# Hydra_OSP.net
KiCad netlist of a schematic drawn in EAGLE
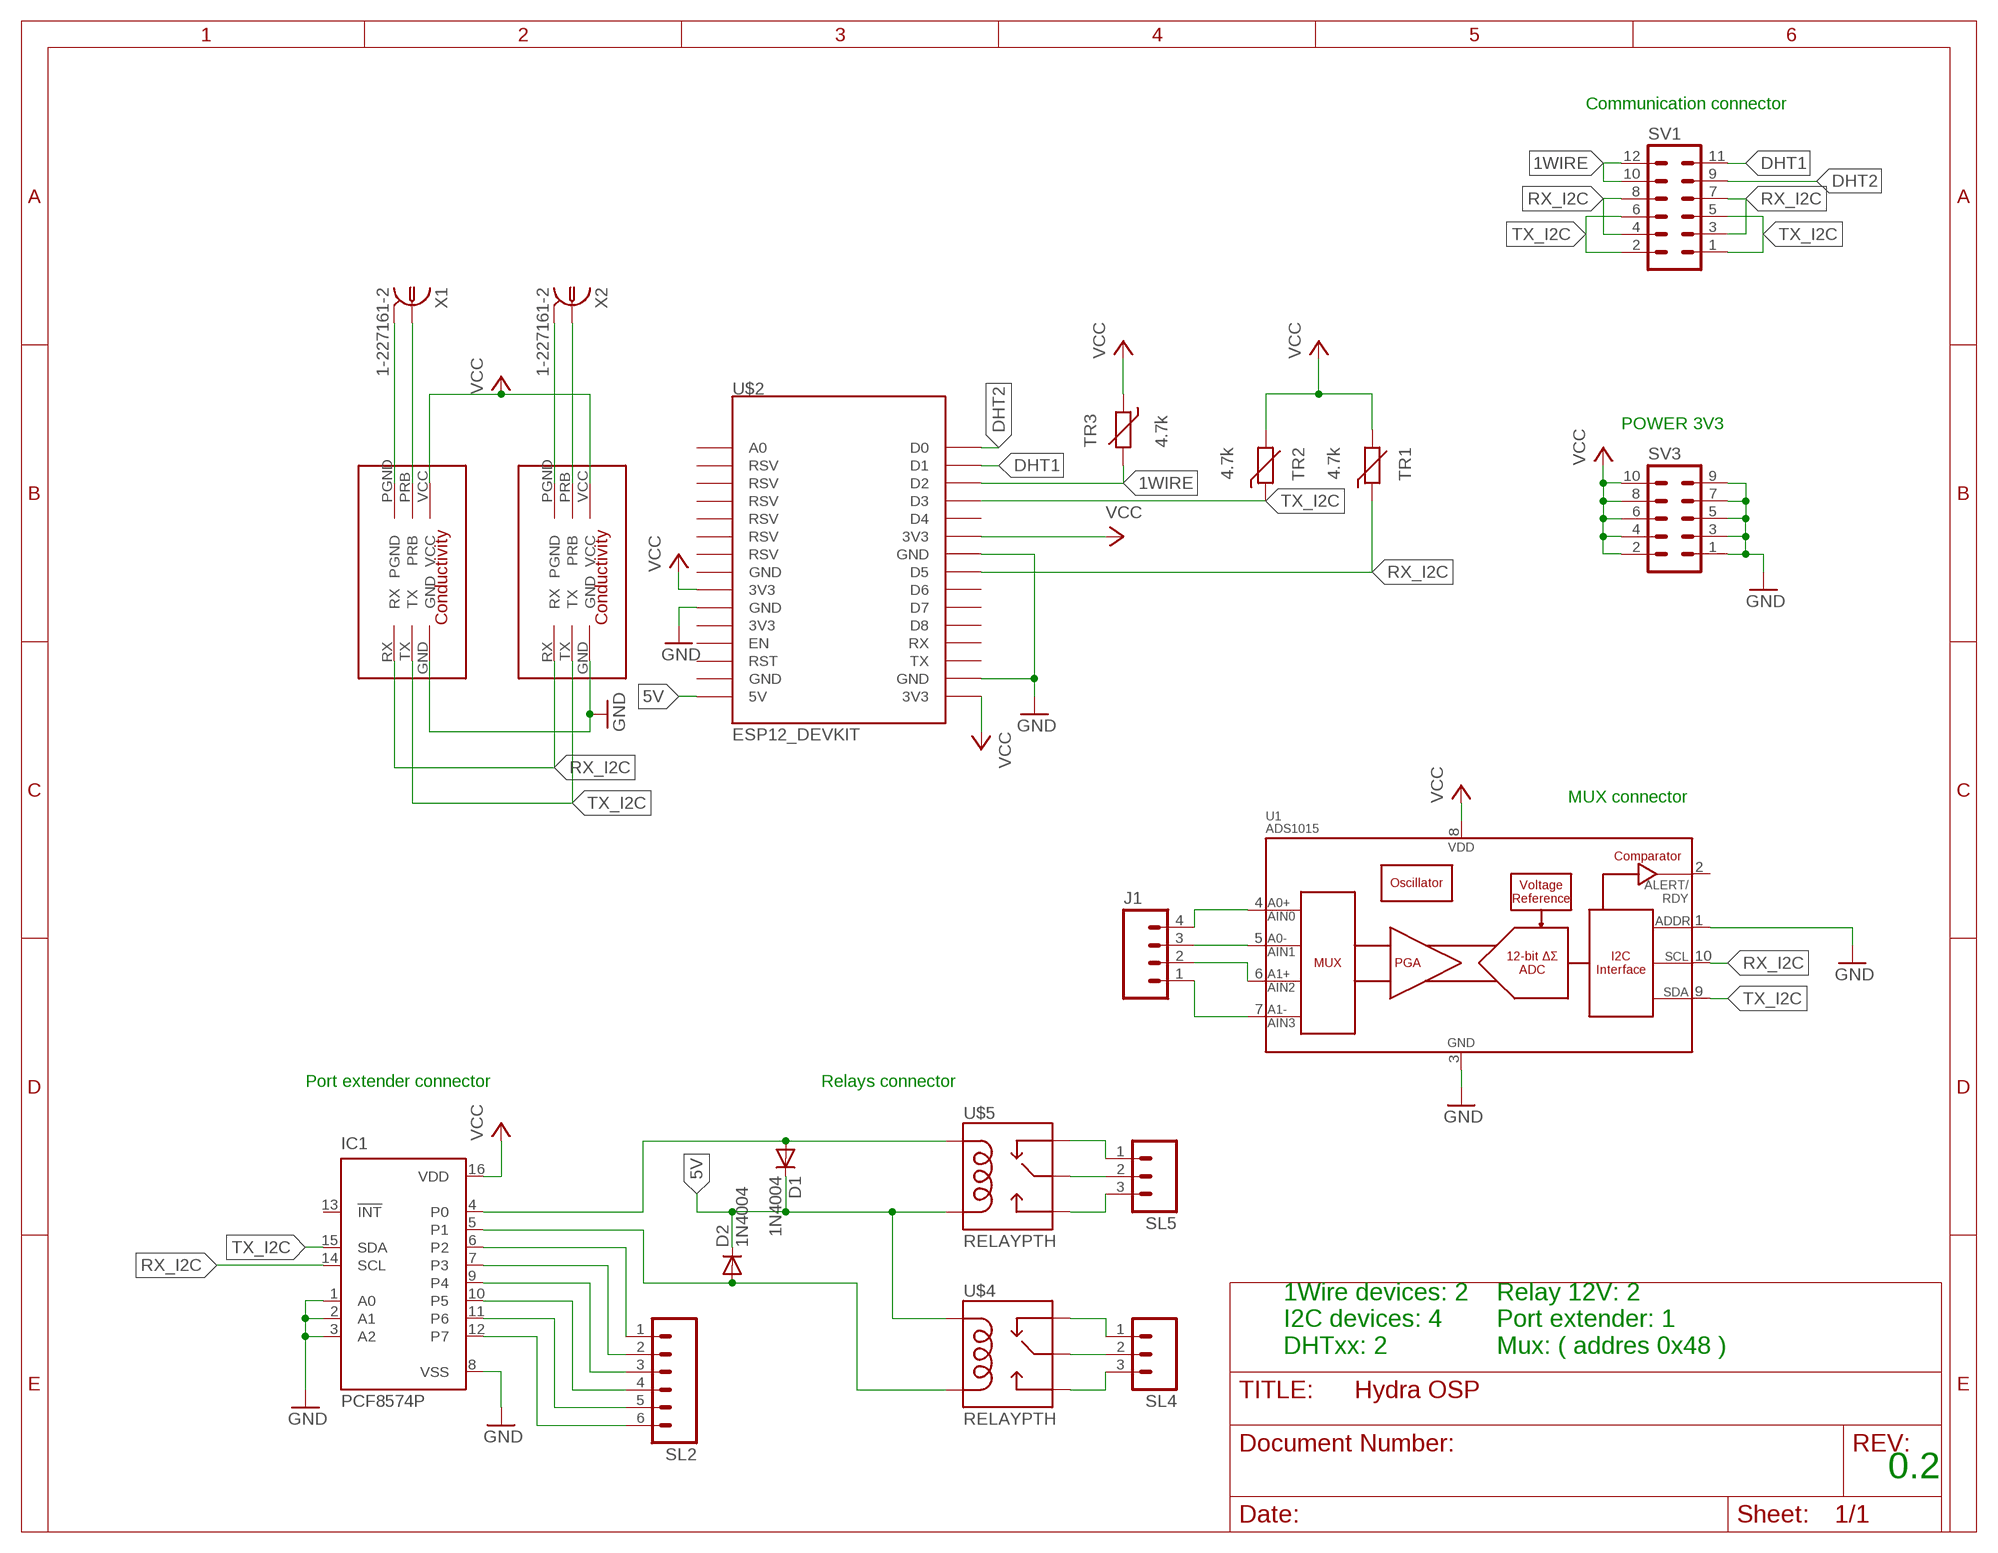
[diagram p0: schematic, sheet 1]

(export (version "E")
  (design (tool "Eeschema 10.0.6"))
  (components
    (comp (ref "D1")
      (value "1N4004")
      (footprint "eagle-import:DO41-10")
      (libsource (lib "eagle-import") (part "1N4004"))
    )
    (comp (ref "D2")
      (value "1N4004")
      (footprint "eagle-import:DO41-10")
      (libsource (lib "eagle-import") (part "1N4004"))
    )
    (comp (ref "IC1")
      (value "PCF8574P")
      (footprint "eagle-import:DIL16")
      (fields (field (name "MPN") "PCF8574PN"))
      (libsource (lib "eagle-import") (part "PCF8574P"))
    )
    (comp (ref "J1")
      (value "M04LOCK")
      (footprint "eagle-import:1X04_LOCK")
      (libsource (lib "eagle-import") (part "M04LOCK"))
    )
    (comp (ref "SL2")
      (value "M06")
      (footprint "eagle-import:06P")
      (libsource (lib "eagle-import") (part "M06"))
    )
    (comp (ref "SL4")
      (value "M03")
      (footprint "eagle-import:03P")
      (libsource (lib "eagle-import") (part "M03"))
    )
    (comp (ref "SL5")
      (value "M03")
      (footprint "eagle-import:03P")
      (libsource (lib "eagle-import") (part "M03"))
    )
    (comp (ref "SV1")
      (value "MA06-2")
      (footprint "eagle-import:MA06-2")
      (libsource (lib "eagle-import") (part "MA06-2"))
    )
    (comp (ref "SV3")
      (value "MA05-2")
      (footprint "eagle-import:MA05-2")
      (libsource (lib "eagle-import") (part "MA05-2"))
    )
    (comp (ref "TR1")
      (value "4.7k")
      (footprint "eagle-import:R-5")
      (libsource (lib "eagle-import") (part "THERMISTOR_R-5"))
    )
    (comp (ref "TR2")
      (value "4.7k")
      (footprint "eagle-import:R-5")
      (libsource (lib "eagle-import") (part "THERMISTOR_R-5"))
    )
    (comp (ref "TR3")
      (value "4.7k")
      (footprint "eagle-import:R-5")
      (libsource (lib "eagle-import") (part "THERMISTOR_R-5"))
    )
    (comp (ref "U$1")
      (value "ATLSCI_COND")
      (footprint "eagle-import:ATLAS_SCI_COND")
      (libsource (lib "eagle-import") (part "ATLSCI_COND"))
    )
    (comp (ref "U$2")
      (value "ESP12_DEVKIT")
      (footprint "eagle-import:ESP12_DEVKIT")
      (libsource (lib "eagle-import") (part "ESP12_DEVKIT"))
    )
    (comp (ref "U$3")
      (value "ATLSCI_COND")
      (footprint "eagle-import:ATLAS_SCI_COND")
      (libsource (lib "eagle-import") (part "ATLSCI_COND"))
    )
    (comp (ref "U$4")
      (value "RELAYPTH")
      (footprint "eagle-import:SRD-05VDC-SL-C")
      (libsource (lib "eagle-import") (part "RELAYPTH"))
    )
    (comp (ref "U$5")
      (value "RELAYPTH")
      (footprint "eagle-import:SRD-05VDC-SL-C")
      (libsource (lib "eagle-import") (part "RELAYPTH"))
    )
    (comp (ref "U1")
      (value "ADS1015")
      (footprint "eagle-import:MSOP10")
      (libsource (lib "eagle-import") (part "ADS1015"))
    )
    (comp (ref "X1")
      (value "1-227161-2")
      (footprint "eagle-import:AMP_227161")
      (libsource (lib "eagle-import") (part "?2271611--2"))
    )
    (comp (ref "X2")
      (value "1-227161-2")
      (footprint "eagle-import:AMP_227161")
      (libsource (lib "eagle-import") (part "?2271611--2"))
    )
  )
  (nets
    (net (code "1") (name "1WIRE") (class "Default")
      (node (ref "SV1") (pin "10") (pinfunction "10_10") (pintype "passive"))
      (node (ref "SV1") (pin "12") (pinfunction "12_12") (pintype "passive"))
      (node (ref "TR3") (pin "2") (pinfunction "2_2") (pintype "passive"))
      (node (ref "U$2") (pin "D2") (pinfunction "D2_D2") (pintype "bidirectional"))
    )
    (net (code "2") (name "5V") (class "Default")
      (node (ref "D1") (pin "C") (pinfunction "C_C") (pintype "passive"))
      (node (ref "D2") (pin "C") (pinfunction "C_C") (pintype "passive"))
      (node (ref "U$2") (pin "5V") (pinfunction "5V_5V") (pintype "bidirectional"))
      (node (ref "U$4") (pin "COIL1") (pinfunction "COIL1_COIL1") (pintype "bidirectional"))
      (node (ref "U$5") (pin "COIL0") (pinfunction "COIL0_COIL0") (pintype "bidirectional"))
    )
    (net (code "3") (name "DHT1") (class "Default")
      (node (ref "SV1") (pin "11") (pinfunction "11_11") (pintype "passive"))
      (node (ref "U$2") (pin "D1") (pinfunction "D1_D1") (pintype "bidirectional"))
    )
    (net (code "4") (name "DHT2") (class "Default")
      (node (ref "SV1") (pin "9") (pinfunction "9_9") (pintype "passive"))
      (node (ref "U$2") (pin "D0") (pinfunction "D0_D0") (pintype "bidirectional"))
    )
    (net (code "5") (name "GND") (class "Default")
      (node (ref "IC1") (pin "1") (pinfunction "A0_1") (pintype "input"))
      (node (ref "IC1") (pin "2") (pinfunction "A1_2") (pintype "input"))
      (node (ref "IC1") (pin "3") (pinfunction "A2_3") (pintype "input"))
      (node (ref "IC1") (pin "8") (pinfunction "VSS_8") (pintype "power_in"))
      (node (ref "SV3") (pin "1") (pinfunction "1_1") (pintype "passive"))
      (node (ref "SV3") (pin "3") (pinfunction "3_3") (pintype "passive"))
      (node (ref "SV3") (pin "5") (pinfunction "5_5") (pintype "passive"))
      (node (ref "SV3") (pin "7") (pinfunction "7_7") (pintype "passive"))
      (node (ref "SV3") (pin "9") (pinfunction "9_9") (pintype "passive"))
      (node (ref "U$1") (pin "GND") (pinfunction "GND_GND") (pintype "bidirectional"))
      (node (ref "U$2") (pin "GND@0") (pinfunction "GND_GND@0") (pintype "bidirectional"))
      (node (ref "U$2") (pin "GND@2") (pinfunction "GND_GND@2") (pintype "bidirectional"))
      (node (ref "U$2") (pin "GND@3") (pinfunction "GND_GND@3") (pintype "bidirectional"))
      (node (ref "U$3") (pin "GND") (pinfunction "GND_GND") (pintype "bidirectional"))
      (node (ref "U1") (pin "1") (pinfunction "ADDR_1") (pintype "bidirectional"))
      (node (ref "U1") (pin "3") (pinfunction "VSS_3") (pintype "bidirectional"))
    )
    (net (code "6") (name "Net-(IC1-P0)") (class "Default")
      (node (ref "D1") (pin "A") (pinfunction "A_A") (pintype "passive"))
      (node (ref "IC1") (pin "4") (pinfunction "P0_4") (pintype "bidirectional"))
      (node (ref "U$5") (pin "COIL1") (pinfunction "COIL1_COIL1") (pintype "bidirectional"))
    )
    (net (code "7") (name "Net-(IC1-P1)") (class "Default")
      (node (ref "D2") (pin "A") (pinfunction "A_A") (pintype "passive"))
      (node (ref "IC1") (pin "5") (pinfunction "P1_5") (pintype "bidirectional"))
      (node (ref "U$4") (pin "COIL0") (pinfunction "COIL0_COIL0") (pintype "bidirectional"))
    )
    (net (code "8") (name "Net-(IC1-P2)") (class "Default")
      (node (ref "IC1") (pin "6") (pinfunction "P2_6") (pintype "bidirectional"))
      (node (ref "SL2") (pin "1") (pinfunction "1_1") (pintype "passive"))
    )
    (net (code "9") (name "Net-(IC1-P3)") (class "Default")
      (node (ref "IC1") (pin "7") (pinfunction "P3_7") (pintype "bidirectional"))
      (node (ref "SL2") (pin "2") (pinfunction "2_2") (pintype "passive"))
    )
    (net (code "10") (name "Net-(IC1-P4)") (class "Default")
      (node (ref "IC1") (pin "9") (pinfunction "P4_9") (pintype "bidirectional"))
      (node (ref "SL2") (pin "3") (pinfunction "3_3") (pintype "passive"))
    )
    (net (code "11") (name "Net-(IC1-P5)") (class "Default")
      (node (ref "IC1") (pin "10") (pinfunction "P5_10") (pintype "bidirectional"))
      (node (ref "SL2") (pin "4") (pinfunction "4_4") (pintype "passive"))
    )
    (net (code "12") (name "Net-(IC1-P6)") (class "Default")
      (node (ref "IC1") (pin "11") (pinfunction "P6_11") (pintype "bidirectional"))
      (node (ref "SL2") (pin "5") (pinfunction "5_5") (pintype "passive"))
    )
    (net (code "13") (name "Net-(IC1-P7)") (class "Default")
      (node (ref "IC1") (pin "12") (pinfunction "P7_12") (pintype "bidirectional"))
      (node (ref "SL2") (pin "6") (pinfunction "6_6") (pintype "passive"))
    )
    (net (code "14") (name "Net-(SL4-Pad2)") (class "Default")
      (node (ref "SL4") (pin "2") (pinfunction "2_2") (pintype "passive"))
      (node (ref "U$4") (pin "SWCOMMON") (pinfunction "SWCOMMON_SWCOMMON") (pintype "bidirectional"))
    )
    (net (code "15") (name "Net-(SL4-Pad3)") (class "Default")
      (node (ref "SL4") (pin "3") (pinfunction "3_3") (pintype "passive"))
      (node (ref "U$4") (pin "SWOPEN") (pinfunction "SWOPEN_SWOPEN") (pintype "bidirectional"))
    )
    (net (code "16") (name "Net-(SL5-Pad2)") (class "Default")
      (node (ref "SL5") (pin "2") (pinfunction "2_2") (pintype "passive"))
      (node (ref "U$5") (pin "SWCOMMON") (pinfunction "SWCOMMON_SWCOMMON") (pintype "bidirectional"))
    )
    (net (code "17") (name "Net-(SL5-Pad3)") (class "Default")
      (node (ref "SL5") (pin "3") (pinfunction "3_3") (pintype "passive"))
      (node (ref "U$5") (pin "SWOPEN") (pinfunction "SWOPEN_SWOPEN") (pintype "bidirectional"))
    )
    (net (code "18") (name "Net-(U$1-PadPGND)") (class "Default")
      (node (ref "U$1") (pin "PGND") (pinfunction "PGND_PGND") (pintype "bidirectional"))
      (node (ref "X1") (pin "2") (pinfunction "2_2") (pintype "passive"))
    )
    (net (code "19") (name "Net-(U$1-PadPRB)") (class "Default")
      (node (ref "U$1") (pin "PRB") (pinfunction "PRB_PRB") (pintype "bidirectional"))
      (node (ref "X1") (pin "1") (pinfunction "1_1") (pintype "passive"))
    )
    (net (code "20") (name "Net-(U$3-PadPGND)") (class "Default")
      (node (ref "U$3") (pin "PGND") (pinfunction "PGND_PGND") (pintype "bidirectional"))
      (node (ref "X2") (pin "2") (pinfunction "2_2") (pintype "passive"))
    )
    (net (code "21") (name "Net-(U$3-PadPRB)") (class "Default")
      (node (ref "U$3") (pin "PRB") (pinfunction "PRB_PRB") (pintype "bidirectional"))
      (node (ref "X2") (pin "1") (pinfunction "1_1") (pintype "passive"))
    )
    (net (code "22") (name "Net-(U$4-SWCLOSE)") (class "Default")
      (node (ref "SL4") (pin "1") (pinfunction "1_1") (pintype "passive"))
      (node (ref "U$4") (pin "SWCLOSED") (pinfunction "SWCLOSE_SWCLOSED") (pintype "bidirectional"))
    )
    (net (code "23") (name "Net-(U$5-SWCLOSE)") (class "Default")
      (node (ref "SL5") (pin "1") (pinfunction "1_1") (pintype "passive"))
      (node (ref "U$5") (pin "SWCLOSED") (pinfunction "SWCLOSE_SWCLOSED") (pintype "bidirectional"))
    )
    (net (code "24") (name "Net-(U1-AIN0)") (class "Default")
      (node (ref "J1") (pin "4") (pinfunction "4_4") (pintype "passive"))
      (node (ref "U1") (pin "4") (pinfunction "AIN0_4") (pintype "bidirectional"))
    )
    (net (code "25") (name "Net-(U1-AIN1)") (class "Default")
      (node (ref "J1") (pin "3") (pinfunction "3_3") (pintype "passive"))
      (node (ref "U1") (pin "5") (pinfunction "AIN1_5") (pintype "bidirectional"))
    )
    (net (code "26") (name "Net-(U1-AIN2)") (class "Default")
      (node (ref "J1") (pin "2") (pinfunction "2_2") (pintype "passive"))
      (node (ref "U1") (pin "6") (pinfunction "AIN2_6") (pintype "bidirectional"))
    )
    (net (code "27") (name "Net-(U1-AIN3)") (class "Default")
      (node (ref "J1") (pin "1") (pinfunction "1_1") (pintype "passive"))
      (node (ref "U1") (pin "7") (pinfunction "AIN3_7") (pintype "bidirectional"))
    )
    (net (code "28") (name "RX_I2C") (class "Default")
      (node (ref "IC1") (pin "14") (pinfunction "SCL_14") (pintype "input"))
      (node (ref "SV1") (pin "3") (pinfunction "3_3") (pintype "passive"))
      (node (ref "SV1") (pin "4") (pinfunction "4_4") (pintype "passive"))
      (node (ref "SV1") (pin "7") (pinfunction "7_7") (pintype "passive"))
      (node (ref "SV1") (pin "8") (pinfunction "8_8") (pintype "passive"))
      (node (ref "TR1") (pin "1") (pinfunction "1_1") (pintype "passive"))
      (node (ref "U$1") (pin "RX") (pinfunction "RX_RX") (pintype "bidirectional"))
      (node (ref "U$2") (pin "D5") (pinfunction "D5_D5") (pintype "bidirectional"))
      (node (ref "U$3") (pin "RX") (pinfunction "RX_RX") (pintype "bidirectional"))
      (node (ref "U1") (pin "10") (pinfunction "SCL_10") (pintype "bidirectional"))
    )
    (net (code "29") (name "TX_I2C") (class "Default")
      (node (ref "IC1") (pin "15") (pinfunction "SDA_15") (pintype "bidirectional"))
      (node (ref "SV1") (pin "1") (pinfunction "1_1") (pintype "passive"))
      (node (ref "SV1") (pin "2") (pinfunction "2_2") (pintype "passive"))
      (node (ref "SV1") (pin "5") (pinfunction "5_5") (pintype "passive"))
      (node (ref "SV1") (pin "6") (pinfunction "6_6") (pintype "passive"))
      (node (ref "TR2") (pin "1") (pinfunction "1_1") (pintype "passive"))
      (node (ref "U$1") (pin "TX") (pinfunction "TX_TX") (pintype "bidirectional"))
      (node (ref "U$2") (pin "D3") (pinfunction "D3_D3") (pintype "bidirectional"))
      (node (ref "U$3") (pin "TX") (pinfunction "TX_TX") (pintype "bidirectional"))
      (node (ref "U1") (pin "9") (pinfunction "SDA_9") (pintype "bidirectional"))
    )
    (net (code "30") (name "VCC") (class "Default")
      (node (ref "IC1") (pin "16") (pinfunction "VDD_16") (pintype "power_in"))
      (node (ref "SV3") (pin "10") (pinfunction "10_10") (pintype "passive"))
      (node (ref "SV3") (pin "2") (pinfunction "2_2") (pintype "passive"))
      (node (ref "SV3") (pin "4") (pinfunction "4_4") (pintype "passive"))
      (node (ref "SV3") (pin "6") (pinfunction "6_6") (pintype "passive"))
      (node (ref "SV3") (pin "8") (pinfunction "8_8") (pintype "passive"))
      (node (ref "TR1") (pin "2") (pinfunction "2_2") (pintype "passive"))
      (node (ref "TR2") (pin "2") (pinfunction "2_2") (pintype "passive"))
      (node (ref "TR3") (pin "1") (pinfunction "1_1") (pintype "passive"))
      (node (ref "U$1") (pin "VCC") (pinfunction "VCC_VCC") (pintype "bidirectional"))
      (node (ref "U$2") (pin "3V3@1") (pinfunction "3V3_3V3@1") (pintype "bidirectional"))
      (node (ref "U$2") (pin "3V3@2") (pinfunction "3V3_3V3@2") (pintype "bidirectional"))
      (node (ref "U$2") (pin "3V3@3") (pinfunction "3V3_3V3@3") (pintype "bidirectional"))
      (node (ref "U$3") (pin "VCC") (pinfunction "VCC_VCC") (pintype "bidirectional"))
      (node (ref "U1") (pin "8") (pinfunction "VDD_8") (pintype "bidirectional"))
    )
    (net (code "31") (name "unconnected-(IC1-~{INT}-Pad13)") (class "Default")
      (node (ref "IC1") (pin "13") (pinfunction "~{INT}_13") (pintype "output"))
    )
    (net (code "32") (name "unconnected-(U$2-3V3-Pad3V3@0)") (class "Default")
      (node (ref "U$2") (pin "3V3@0") (pinfunction "3V3_3V3@0") (pintype "bidirectional"))
    )
    (net (code "33") (name "unconnected-(U$2-GND-PadGND@1)") (class "Default")
      (node (ref "U$2") (pin "GND@1") (pinfunction "GND_GND@1") (pintype "bidirectional"))
    )
    (net (code "34") (name "unconnected-(U$2-GND-PadGND@4)") (class "Default")
      (node (ref "U$2") (pin "GND@4") (pinfunction "GND_GND@4") (pintype "bidirectional"))
    )
    (net (code "35") (name "unconnected-(U$2-PadA0)") (class "Default")
      (node (ref "U$2") (pin "A0") (pinfunction "A0_A0") (pintype "bidirectional"))
    )
    (net (code "36") (name "unconnected-(U$2-PadD4)") (class "Default")
      (node (ref "U$2") (pin "D4") (pinfunction "D4_D4") (pintype "bidirectional"))
    )
    (net (code "37") (name "unconnected-(U$2-PadD6)") (class "Default")
      (node (ref "U$2") (pin "D6") (pinfunction "D6_D6") (pintype "bidirectional"))
    )
    (net (code "38") (name "unconnected-(U$2-PadD7)") (class "Default")
      (node (ref "U$2") (pin "D7") (pinfunction "D7_D7") (pintype "bidirectional"))
    )
    (net (code "39") (name "unconnected-(U$2-PadD8)") (class "Default")
      (node (ref "U$2") (pin "D8") (pinfunction "D8_D8") (pintype "bidirectional"))
    )
    (net (code "40") (name "unconnected-(U$2-PadEN)") (class "Default")
      (node (ref "U$2") (pin "EN") (pinfunction "EN_EN") (pintype "bidirectional"))
    )
    (net (code "41") (name "unconnected-(U$2-PadRST)") (class "Default")
      (node (ref "U$2") (pin "RST") (pinfunction "RST_RST") (pintype "bidirectional"))
    )
    (net (code "42") (name "unconnected-(U$2-PadRX)") (class "Default")
      (node (ref "U$2") (pin "RX") (pinfunction "RX_RX") (pintype "bidirectional"))
    )
    (net (code "43") (name "unconnected-(U$2-PadTX)") (class "Default")
      (node (ref "U$2") (pin "TX") (pinfunction "TX_TX") (pintype "bidirectional"))
    )
    (net (code "44") (name "unconnected-(U$2-RSV-PadRSV@0)") (class "Default")
      (node (ref "U$2") (pin "RSV@0") (pinfunction "RSV_RSV@0") (pintype "bidirectional"))
    )
    (net (code "45") (name "unconnected-(U$2-RSV-PadRSV@1)") (class "Default")
      (node (ref "U$2") (pin "RSV@1") (pinfunction "RSV_RSV@1") (pintype "bidirectional"))
    )
    (net (code "46") (name "unconnected-(U$2-RSV-PadRSV@2)") (class "Default")
      (node (ref "U$2") (pin "RSV@2") (pinfunction "RSV_RSV@2") (pintype "bidirectional"))
    )
    (net (code "47") (name "unconnected-(U$2-RSV-PadRSV@3)") (class "Default")
      (node (ref "U$2") (pin "RSV@3") (pinfunction "RSV_RSV@3") (pintype "bidirectional"))
    )
    (net (code "48") (name "unconnected-(U$2-RSV-PadRSV@4)") (class "Default")
      (node (ref "U$2") (pin "RSV@4") (pinfunction "RSV_RSV@4") (pintype "bidirectional"))
    )
    (net (code "49") (name "unconnected-(U$2-RSV-PadRSV@5)") (class "Default")
      (node (ref "U$2") (pin "RSV@5") (pinfunction "RSV_RSV@5") (pintype "bidirectional"))
    )
    (net (code "50") (name "unconnected-(U1-ALERT{slash}RDY-Pad2)") (class "Default")
      (node (ref "U1") (pin "2") (pinfunction "ALERT/RDY_2") (pintype "bidirectional"))
    )
  )
)
